# power.net
KiCad netlist of a schematic drawn in Altium Designer
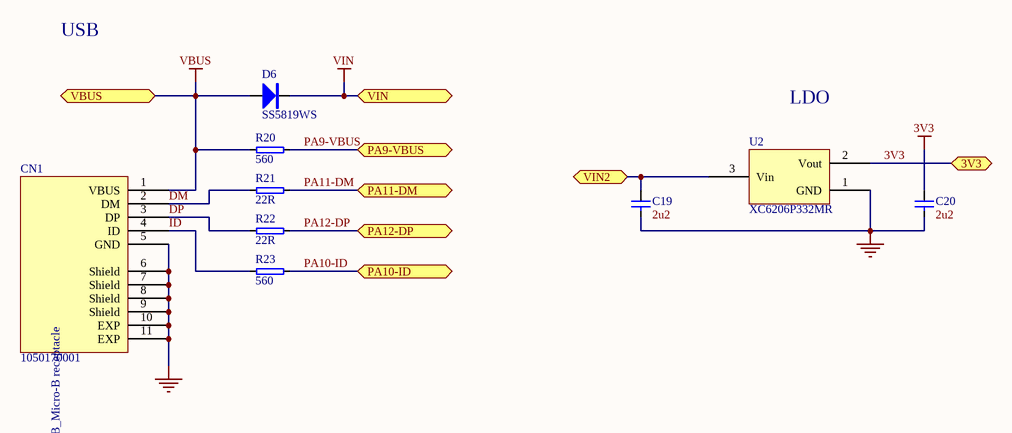
[diagram p0: power.SchDoc]

(export (version "E")
  (design (tool "Eeschema 10.0.6"))
  (components
    (comp (ref "C19") (value "2u2") (footprint "SMD0603") (libsource (lib "s_device") (part "Cap")))
    (comp (ref "C20") (value "2u2") (footprint "SMD0603") (libsource (lib "s_device") (part "Cap")))
    (comp (ref "CN1")
      (value "1050170001")
      (footprint "MOLEX_1050170001")
      (libsource (lib "s_connect") (part "1050170001"))
    )
    (comp (ref "D6")
      (value "SS5819WS")
      (footprint "1N5819-SOD323")
      (libsource (lib "s_device") (part "Diode"))
    )
    (comp (ref "R20") (value "560") (footprint "SMD0402") (libsource (lib "s_device") (part "Res")))
    (comp (ref "R21") (value "22R") (footprint "SMD0402") (libsource (lib "s_device") (part "Res")))
    (comp (ref "R22") (value "22R") (footprint "SMD0402") (libsource (lib "s_device") (part "Res")))
    (comp (ref "R23") (value "560") (footprint "SMD0402") (libsource (lib "s_device") (part "Res")))
    (comp (ref "U2")
      (value "XC6206P332MR")
      (footprint "SOT-23_N")
      (libsource (lib "s_power") (part "XC6206"))
    )
  )
  (nets
    (net (code "1") (name "/DM") (class "Default")
      (node (ref "CN1") (pin "2") (pinfunction "DM_2") (pintype "passive"))
      (node (ref "R21") (pin "2") (pintype "passive"))
    )
    (net (code "2") (name "/DP") (class "Default")
      (node (ref "CN1") (pin "3") (pinfunction "DP_3") (pintype "passive"))
      (node (ref "R22") (pin "2") (pintype "passive"))
    )
    (net (code "3") (name "/ID") (class "Default")
      (node (ref "CN1") (pin "4") (pinfunction "ID_4") (pintype "passive"))
      (node (ref "R23") (pin "2") (pintype "passive"))
    )
    (net (code "4") (name "/PA9-VBUS") (class "Default") (node (ref "R20") (pin "1") (pintype "passive")))
    (net (code "5") (name "/PA10-ID") (class "Default") (node (ref "R23") (pin "1") (pintype "passive")))
    (net (code "6") (name "/PA11-DM") (class "Default") (node (ref "R21") (pin "1") (pintype "passive")))
    (net (code "7") (name "/PA12-DP") (class "Default") (node (ref "R22") (pin "1") (pintype "passive")))
    (net (code "8") (name "/VIN2") (class "Default")
      (node (ref "C19") (pin "2") (pintype "passive"))
      (node (ref "U2") (pin "3") (pinfunction "Vin_3") (pintype "passive"))
    )
    (net (code "9") (name "3V3") (class "Default")
      (node (ref "C20") (pin "2") (pintype "passive"))
      (node (ref "U2") (pin "2") (pinfunction "Vout_2") (pintype "passive"))
    )
    (net (code "10") (name "GND") (class "Default")
      (node (ref "C19") (pin "1") (pintype "passive"))
      (node (ref "C20") (pin "1") (pintype "passive"))
      (node (ref "CN1") (pin "10") (pinfunction "EXP_10") (pintype "passive"))
      (node (ref "CN1") (pin "11") (pinfunction "EXP_11") (pintype "passive"))
      (node (ref "CN1") (pin "5") (pinfunction "GND_5") (pintype "passive"))
      (node (ref "CN1") (pin "6") (pinfunction "Shield_6") (pintype "passive"))
      (node (ref "CN1") (pin "7") (pinfunction "Shield_7") (pintype "passive"))
      (node (ref "CN1") (pin "8") (pinfunction "Shield_8") (pintype "passive"))
      (node (ref "CN1") (pin "9") (pinfunction "Shield_9") (pintype "passive"))
      (node (ref "U2") (pin "1") (pinfunction "GND_1") (pintype "passive"))
    )
    (net (code "11") (name "VBUS") (class "Default")
      (node (ref "CN1") (pin "1") (pinfunction "VBUS_1") (pintype "passive"))
      (node (ref "D6") (pin "1") (pintype "passive"))
      (node (ref "R20") (pin "2") (pintype "passive"))
    )
    (net (code "12") (name "VIN") (class "Default") (node (ref "D6") (pin "2") (pintype "passive")))
  )
)
